# plug-v20-Make-board-myself-to-test-circu.net
KiCad netlist of a schematic drawn in EAGLE
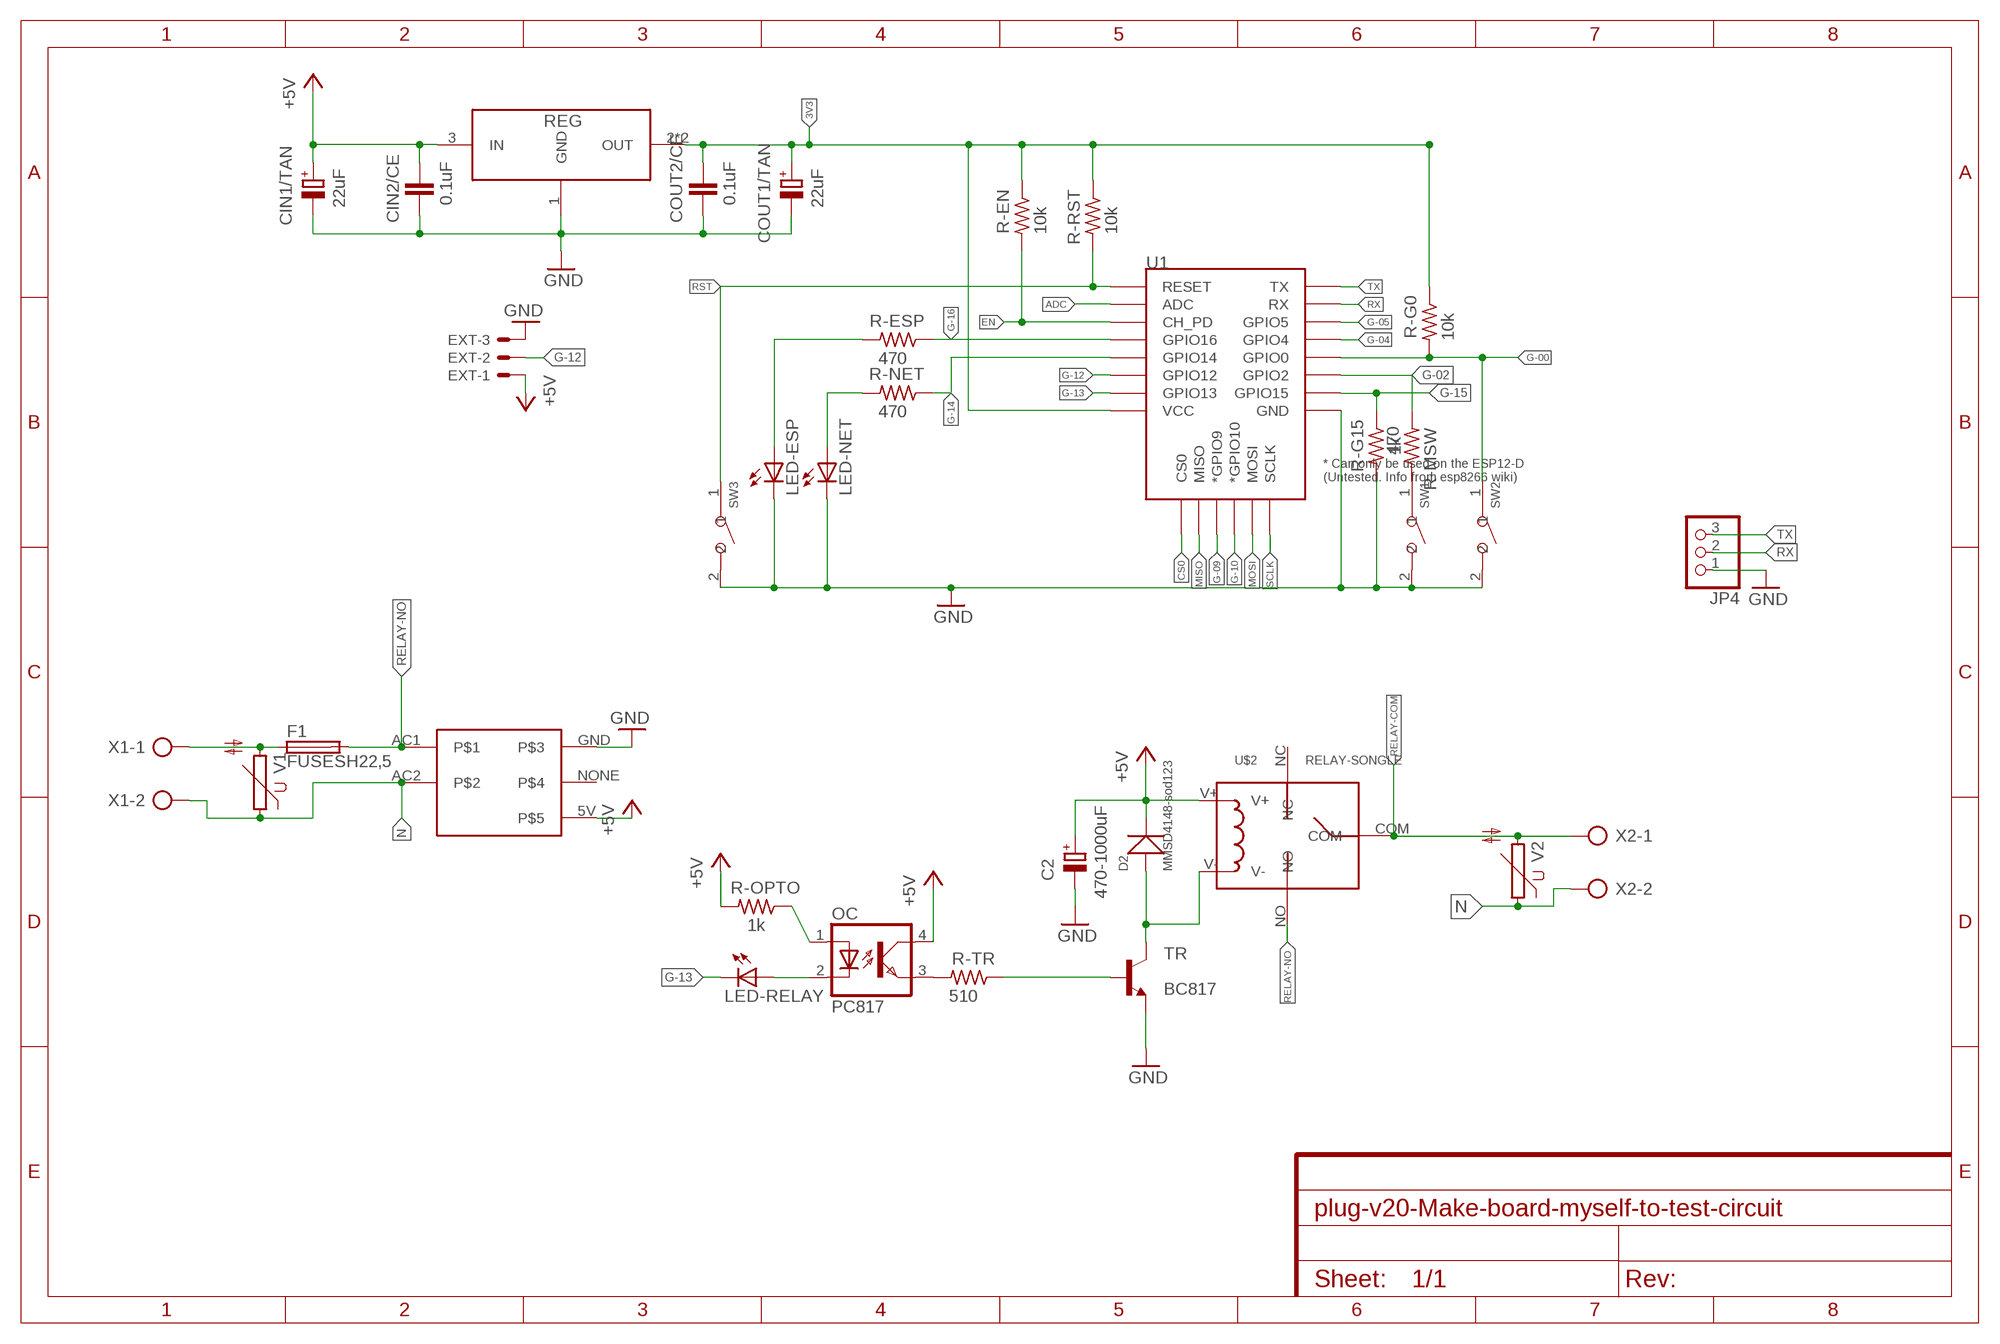
[diagram p0: schematic, sheet 1]

(export (version "E")
  (design (tool "Eeschema 10.0.6"))
  (components
    (comp (ref "C2")
      (value "470-1000uF")
      (footprint "eagle-import:E3,5-8")
      (libsource (lib "eagle-import") (part "CPOL-EUE3.5-8"))
    )
    (comp (ref "CIN1/TAN")
      (value "22uF")
      (footprint "eagle-import:B_3528-21R")
      (libsource (lib "eagle-import") (part "CPOL-EUB/3528-21R"))
    )
    (comp (ref "CIN2/CE")
      (value "0.1uF")
      (footprint "eagle-import:C0805K")
      (libsource (lib "eagle-import") (part "C-EUC0805K"))
    )
    (comp (ref "COUT1/TAN")
      (value "22uF")
      (footprint "eagle-import:B_3528-21R")
      (libsource (lib "eagle-import") (part "CPOL-EUB/3528-21R"))
    )
    (comp (ref "COUT2/CE")
      (value "0.1uF")
      (footprint "eagle-import:C0805K")
      (libsource (lib "eagle-import") (part "C-EUC0805K"))
    )
    (comp (ref "D2")
      (value "MMSD4148-sod123")
      (footprint "eagle-import:SOD-123")
      (fields (field (name "MPN") "MMSD4148"))
      (libsource (lib "eagle-import") (part "SMD-DIODE-100V-200MA(SOD-123)"))
    )
    (comp (ref "EXT")
      (value "53048-03")
      (footprint "eagle-import:53048-03")
      (fields (field (name "MF") "WALDOM/MOLEX") (field (name "MPN") "53048-0310"))
      (libsource (lib "eagle-import") (part "53?-03048"))
    )
    (comp (ref "F1")
      (value "FUSESH22,5")
      (footprint "eagle-import:SH22,5")
      (libsource (lib "eagle-import") (part "FUSESH22,5"))
    )
    (comp (ref "JP4")
      (value "PINHD-1X3")
      (footprint "eagle-import:1X03")
      (libsource (lib "eagle-import") (part "PINHD-1X3"))
    )
    (comp (ref "LED-ESP")
      (value "LEDCHIPLED_0805")
      (footprint "eagle-import:CHIPLED_0805")
      (libsource (lib "eagle-import") (part "LEDCHIPLED_0805"))
    )
    (comp (ref "LED-NET")
      (value "LEDCHIPLED_0805")
      (footprint "eagle-import:CHIPLED_0805")
      (libsource (lib "eagle-import") (part "LEDCHIPLED_0805"))
    )
    (comp (ref "LED-RELAY")
      (value "LEDCHIPLED_0805")
      (footprint "eagle-import:CHIPLED_0805")
      (libsource (lib "eagle-import") (part "LEDCHIPLED_0805"))
    )
    (comp (ref "OC")
      (value "PC817")
      (footprint "eagle-import:DIL04")
      (fields (field (name "MPN") "PC817X4J000F"))
      (libsource (lib "eagle-import") (part "PC817"))
    )
    (comp (ref "R-EN")
      (value "10k")
      (footprint "eagle-import:M0805")
      (libsource (lib "eagle-import") (part "R-US_M0805"))
    )
    (comp (ref "R-ESP")
      (value "470")
      (footprint "eagle-import:M0805")
      (libsource (lib "eagle-import") (part "R-US_M0805"))
    )
    (comp (ref "R-G0")
      (value "10k")
      (footprint "eagle-import:M0805")
      (libsource (lib "eagle-import") (part "R-US_M0805"))
    )
    (comp (ref "R-G15")
      (value "1k")
      (footprint "eagle-import:M0805")
      (libsource (lib "eagle-import") (part "R-US_M0805"))
    )
    (comp (ref "R-MSW")
      (value "470")
      (footprint "eagle-import:M0805")
      (libsource (lib "eagle-import") (part "R-US_M0805"))
    )
    (comp (ref "R-NET")
      (value "470")
      (footprint "eagle-import:M0805")
      (libsource (lib "eagle-import") (part "R-US_M0805"))
    )
    (comp (ref "R-OPTO")
      (value "1k")
      (footprint "eagle-import:M0805")
      (libsource (lib "eagle-import") (part "R-US_M0805"))
    )
    (comp (ref "R-RST")
      (value "10k")
      (footprint "eagle-import:M0805")
      (libsource (lib "eagle-import") (part "R-US_M0805"))
    )
    (comp (ref "R-TR")
      (value "510")
      (footprint "eagle-import:M0805")
      (libsource (lib "eagle-import") (part "R-US_M0805"))
    )
    (comp (ref "REG")
      (value "AMS1117-3.3")
      (footprint "eagle-import:SOT-223")
      (libsource (lib "eagle-import") (part "AMS1117-3.3"))
    )
    (comp (ref "SW1")
      (value "DIP-BUTTON(2P-6.0X3.0X4.3MM)-TS-1101F")
      (footprint "eagle-import:SW2-5.0-6.0X3.0X4.3MM")
      (libsource (lib "eagle-import") (part "DIP-BUTTON(2P-6.0X3.0X4.3MM)-TS-1101F"))
    )
    (comp (ref "SW2")
      (value "DIP-BUTTON(2P-6.0X3.0X4.3MM)-TS-1101F")
      (footprint "eagle-import:SW2-5.0-6.0X3.0X4.3MM")
      (libsource (lib "eagle-import") (part "DIP-BUTTON(2P-6.0X3.0X4.3MM)-TS-1101F"))
    )
    (comp (ref "SW3")
      (value "DIP-BUTTON(2P-6.0X3.0X4.3MM)-TS-1101F")
      (footprint "eagle-import:SW2-5.0-6.0X3.0X4.3MM")
      (libsource (lib "eagle-import") (part "DIP-BUTTON(2P-6.0X3.0X4.3MM)-TS-1101F"))
    )
    (comp (ref "TR")
      (value "BC817")
      (footprint "eagle-import:SOT23-BEC")
      (libsource (lib "eagle-import") (part "BC817SMD-16"))
    )
    (comp (ref "U$2")
      (value "RELAY-SONGLE")
      (footprint "eagle-import:RELAY-SONGLE")
      (libsource (lib "eagle-import") (part "RELAY-SONGLE"))
    )
    (comp (ref "U$4")
      (value "POWERSUPPLY-5V-700MA")
      (footprint "eagle-import:POWERSUPPLY-5V-700MA")
      (libsource (lib "eagle-import") (part "POWERSUPPLY-5V-700MA"))
    )
    (comp (ref "U1")
      (value "ESP12ESMD")
      (footprint "eagle-import:ESP12E-SMD")
      (libsource (lib "eagle-import") (part "ESP12ESMD"))
    )
    (comp (ref "V1")
      (value "S14K11")
      (footprint "eagle-import:S14K11")
      (libsource (lib "eagle-import") (part "S14K11"))
    )
    (comp (ref "V2")
      (value "S14K11")
      (footprint "eagle-import:S14K11")
      (libsource (lib "eagle-import") (part "S14K11"))
    )
    (comp (ref "X1")
      (value "AK300/2")
      (footprint "eagle-import:AK300_2")
      (libsource (lib "eagle-import") (part "AK300/2"))
    )
    (comp (ref "X2")
      (value "AK300/2")
      (footprint "eagle-import:AK300_2")
      (libsource (lib "eagle-import") (part "AK300/2"))
    )
  )
  (nets
    (net (code "1") (name "+5V") (class "Default")
      (node (ref "C2") (pin "+") (pinfunction "+_+") (pintype "passive"))
      (node (ref "CIN1/TAN") (pin "+") (pinfunction "+_+") (pintype "passive"))
      (node (ref "CIN2/CE") (pin "1") (pinfunction "1_1") (pintype "passive"))
      (node (ref "D2") (pin "-") (pinfunction "-_-") (pintype "passive"))
      (node (ref "EXT") (pin "1") (pinfunction "S_1") (pintype "passive"))
      (node (ref "OC") (pin "4") (pinfunction "COL_4") (pintype "passive"))
      (node (ref "R-OPTO") (pin "2") (pinfunction "2_2") (pintype "passive"))
      (node (ref "REG") (pin "3") (pinfunction "IN_3") (pintype "input"))
      (node (ref "U$2") (pin "V+") (pinfunction "V+_V+") (pintype "bidirectional"))
      (node (ref "U$4") (pin "5V") (pinfunction "P$5_5V") (pintype "bidirectional"))
    )
    (net (code "2") (name "3V3") (class "Default")
      (node (ref "COUT1/TAN") (pin "+") (pinfunction "+_+") (pintype "passive"))
      (node (ref "COUT2/CE") (pin "1") (pinfunction "1_1") (pintype "passive"))
      (node (ref "R-EN") (pin "1") (pinfunction "1_1") (pintype "passive"))
      (node (ref "R-G0") (pin "1") (pinfunction "1_1") (pintype "passive"))
      (node (ref "R-RST") (pin "1") (pinfunction "1_1") (pintype "passive"))
      (node (ref "REG") (pin "2") (pinfunction "OUT_2") (pintype "output"))
      (node (ref "REG") (pin "4") (pinfunction "OUT_4") (pintype "output"))
      (node (ref "U1") (pin "VCC") (pinfunction "VCC_VCC") (pintype "bidirectional"))
    )
    (net (code "3") (name "ADC") (class "Default")
      (node (ref "U1") (pin "ADC") (pinfunction "ADC_ADC") (pintype "bidirectional"))
    )
    (net (code "4") (name "CS0") (class "Default")
      (node (ref "U1") (pin "CS0") (pinfunction "CS0_CS0") (pintype "bidirectional"))
    )
    (net (code "5") (name "EN") (class "Default")
      (node (ref "R-EN") (pin "2") (pinfunction "2_2") (pintype "passive"))
      (node (ref "U1") (pin "CH_PD") (pinfunction "CH_PD_CH_PD") (pintype "bidirectional"))
    )
    (net (code "6") (name "G-00") (class "Default")
      (node (ref "R-G0") (pin "2") (pinfunction "2_2") (pintype "passive"))
      (node (ref "SW2") (pin "1") (pinfunction "1_1") (pintype "bidirectional"))
      (node (ref "U1") (pin "GPIO0") (pinfunction "GPIO0_GPIO0") (pintype "bidirectional"))
    )
    (net (code "7") (name "G-02") (class "Default")
      (node (ref "R-MSW") (pin "2") (pinfunction "2_2") (pintype "passive"))
      (node (ref "U1") (pin "GPIO2") (pinfunction "GPIO2_GPIO2") (pintype "bidirectional"))
    )
    (net (code "8") (name "G-04") (class "Default")
      (node (ref "U1") (pin "GPIO4") (pinfunction "GPIO4_GPIO4") (pintype "bidirectional"))
    )
    (net (code "9") (name "G-05") (class "Default")
      (node (ref "U1") (pin "GPIO5") (pinfunction "GPIO5_GPIO5") (pintype "bidirectional"))
    )
    (net (code "10") (name "G-09") (class "Default")
      (node (ref "U1") (pin "GPIO9") (pinfunction "*GPIO9_GPIO9") (pintype "bidirectional"))
    )
    (net (code "11") (name "G-10") (class "Default")
      (node (ref "U1") (pin "GPIO10") (pinfunction "*GPIO10_GPIO10") (pintype "bidirectional"))
    )
    (net (code "12") (name "G-12") (class "Default")
      (node (ref "EXT") (pin "2") (pinfunction "S_2") (pintype "passive"))
      (node (ref "U1") (pin "GPIO12") (pinfunction "GPIO12_GPIO12") (pintype "bidirectional"))
    )
    (net (code "13") (name "G-13") (class "Default")
      (node (ref "LED-RELAY") (pin "C") (pinfunction "C_C") (pintype "passive"))
      (node (ref "U1") (pin "GPIO13") (pinfunction "GPIO13_GPIO13") (pintype "bidirectional"))
    )
    (net (code "14") (name "G-14") (class "Default")
      (node (ref "R-NET") (pin "1") (pinfunction "1_1") (pintype "passive"))
      (node (ref "U1") (pin "GPIO14") (pinfunction "GPIO14_GPIO14") (pintype "bidirectional"))
    )
    (net (code "15") (name "G-15") (class "Default")
      (node (ref "R-G15") (pin "1") (pinfunction "1_1") (pintype "passive"))
      (node (ref "U1") (pin "GPIO15") (pinfunction "GPIO15_GPIO15") (pintype "bidirectional"))
    )
    (net (code "16") (name "G-16") (class "Default")
      (node (ref "R-ESP") (pin "1") (pinfunction "1_1") (pintype "passive"))
      (node (ref "U1") (pin "GPIO16") (pinfunction "GPIO16_GPIO16") (pintype "bidirectional"))
    )
    (net (code "17") (name "GND") (class "Default")
      (node (ref "C2") (pin "-") (pinfunction "-_-") (pintype "passive"))
      (node (ref "CIN1/TAN") (pin "-") (pinfunction "-_-") (pintype "passive"))
      (node (ref "CIN2/CE") (pin "2") (pinfunction "2_2") (pintype "passive"))
      (node (ref "COUT1/TAN") (pin "-") (pinfunction "-_-") (pintype "passive"))
      (node (ref "COUT2/CE") (pin "2") (pinfunction "2_2") (pintype "passive"))
      (node (ref "EXT") (pin "3") (pinfunction "S_3") (pintype "passive"))
      (node (ref "JP4") (pin "1") (pinfunction "1_1") (pintype "passive"))
      (node (ref "LED-ESP") (pin "C") (pinfunction "C_C") (pintype "passive"))
      (node (ref "LED-NET") (pin "C") (pinfunction "C_C") (pintype "passive"))
      (node (ref "R-G15") (pin "2") (pinfunction "2_2") (pintype "passive"))
      (node (ref "REG") (pin "1") (pinfunction "GND_1") (pintype "passive"))
      (node (ref "SW1") (pin "2") (pinfunction "2_2") (pintype "bidirectional"))
      (node (ref "SW2") (pin "2") (pinfunction "2_2") (pintype "bidirectional"))
      (node (ref "SW3") (pin "2") (pinfunction "2_2") (pintype "bidirectional"))
      (node (ref "TR") (pin "E") (pinfunction "E_E") (pintype "passive"))
      (node (ref "U$4") (pin "GND") (pinfunction "P$3_GND") (pintype "bidirectional"))
      (node (ref "U1") (pin "GND") (pinfunction "GND_GND") (pintype "bidirectional"))
    )
    (net (code "18") (name "MISO") (class "Default")
      (node (ref "U1") (pin "MISO") (pinfunction "MISO_MISO") (pintype "bidirectional"))
    )
    (net (code "19") (name "MOSI") (class "Default")
      (node (ref "U1") (pin "MOSI") (pinfunction "MOSI_MOSI") (pintype "bidirectional"))
    )
    (net (code "20") (name "N") (class "Default")
      (node (ref "U$4") (pin "AC2") (pinfunction "P$2_AC2") (pintype "bidirectional"))
      (node (ref "V1") (pin "1") (pinfunction "1_1") (pintype "passive"))
      (node (ref "V2") (pin "1") (pinfunction "1_1") (pintype "passive"))
      (node (ref "X1") (pin "2") (pinfunction "KL_2") (pintype "passive"))
      (node (ref "X2") (pin "2") (pinfunction "KL_2") (pintype "passive"))
    )
    (net (code "21") (name "Net-(D2-Pad+)") (class "Default")
      (node (ref "D2") (pin "+") (pinfunction "+_+") (pintype "passive"))
      (node (ref "TR") (pin "C") (pinfunction "C_C") (pintype "passive"))
      (node (ref "U$2") (pin "V-") (pinfunction "V-_V-") (pintype "bidirectional"))
    )
    (net (code "22") (name "Net-(LED-ESP-PadA)") (class "Default")
      (node (ref "LED-ESP") (pin "A") (pinfunction "A_A") (pintype "passive"))
      (node (ref "R-ESP") (pin "2") (pinfunction "2_2") (pintype "passive"))
    )
    (net (code "23") (name "Net-(LED-NET-PadA)") (class "Default")
      (node (ref "LED-NET") (pin "A") (pinfunction "A_A") (pintype "passive"))
      (node (ref "R-NET") (pin "2") (pinfunction "2_2") (pintype "passive"))
    )
    (net (code "24") (name "Net-(OC-A)") (class "Default")
      (node (ref "OC") (pin "1") (pinfunction "A_1") (pintype "passive"))
      (node (ref "R-OPTO") (pin "1") (pinfunction "1_1") (pintype "passive"))
    )
    (net (code "25") (name "Net-(OC-C)") (class "Default")
      (node (ref "LED-RELAY") (pin "A") (pinfunction "A_A") (pintype "passive"))
      (node (ref "OC") (pin "2") (pinfunction "C_2") (pintype "passive"))
    )
    (net (code "26") (name "Net-(OC-EMIT)") (class "Default")
      (node (ref "OC") (pin "3") (pinfunction "EMIT_3") (pintype "passive"))
      (node (ref "R-TR") (pin "2") (pinfunction "2_2") (pintype "passive"))
    )
    (net (code "27") (name "Net-(R-MSW-Pad1)") (class "Default")
      (node (ref "R-MSW") (pin "1") (pinfunction "1_1") (pintype "passive"))
      (node (ref "SW1") (pin "1") (pinfunction "1_1") (pintype "bidirectional"))
    )
    (net (code "28") (name "Net-(R-TR-Pad1)") (class "Default")
      (node (ref "R-TR") (pin "1") (pinfunction "1_1") (pintype "passive"))
      (node (ref "TR") (pin "B") (pinfunction "B_B") (pintype "passive"))
    )
    (net (code "29") (name "Net-(X1A-KL)") (class "Default")
      (node (ref "F1") (pin "1") (pinfunction "1_1") (pintype "passive"))
      (node (ref "V1") (pin "2") (pinfunction "2_2") (pintype "passive"))
      (node (ref "X1") (pin "1") (pinfunction "KL_1") (pintype "passive"))
    )
    (net (code "30") (name "RELAY-COM") (class "Default")
      (node (ref "U$2") (pin "COM") (pinfunction "COM_COM") (pintype "bidirectional"))
      (node (ref "V2") (pin "2") (pinfunction "2_2") (pintype "passive"))
      (node (ref "X2") (pin "1") (pinfunction "KL_1") (pintype "passive"))
    )
    (net (code "31") (name "RELAY-NO") (class "Default")
      (node (ref "F1") (pin "2") (pinfunction "2_2") (pintype "passive"))
      (node (ref "U$2") (pin "NO") (pinfunction "NO_NO") (pintype "bidirectional"))
      (node (ref "U$4") (pin "AC1") (pinfunction "P$1_AC1") (pintype "bidirectional"))
    )
    (net (code "32") (name "RST") (class "Default")
      (node (ref "R-RST") (pin "2") (pinfunction "2_2") (pintype "passive"))
      (node (ref "SW3") (pin "1") (pinfunction "1_1") (pintype "bidirectional"))
      (node (ref "U1") (pin "RESET") (pinfunction "RESET_RESET") (pintype "bidirectional"))
    )
    (net (code "33") (name "RX") (class "Default")
      (node (ref "JP4") (pin "2") (pinfunction "2_2") (pintype "passive"))
      (node (ref "U1") (pin "RXD0") (pinfunction "RX_RXD0") (pintype "bidirectional"))
    )
    (net (code "34") (name "SCLK") (class "Default")
      (node (ref "U1") (pin "SCLK") (pinfunction "SCLK_SCLK") (pintype "bidirectional"))
    )
    (net (code "35") (name "TX") (class "Default")
      (node (ref "JP4") (pin "3") (pinfunction "3_3") (pintype "passive"))
      (node (ref "U1") (pin "TXD0") (pinfunction "TX_TXD0") (pintype "bidirectional"))
    )
    (net (code "36") (name "unconnected-(U$2-PadNC)") (class "Default")
      (node (ref "U$2") (pin "NC") (pinfunction "NC_NC") (pintype "bidirectional"))
    )
    (net (code "37") (name "unconnected-(U$4-P$4-PadNONE)") (class "Default")
      (node (ref "U$4") (pin "NONE") (pinfunction "P$4_NONE") (pintype "bidirectional"))
    )
  )
)
